# slave.net
KiCad netlist of a schematic drawn in Altium Designer
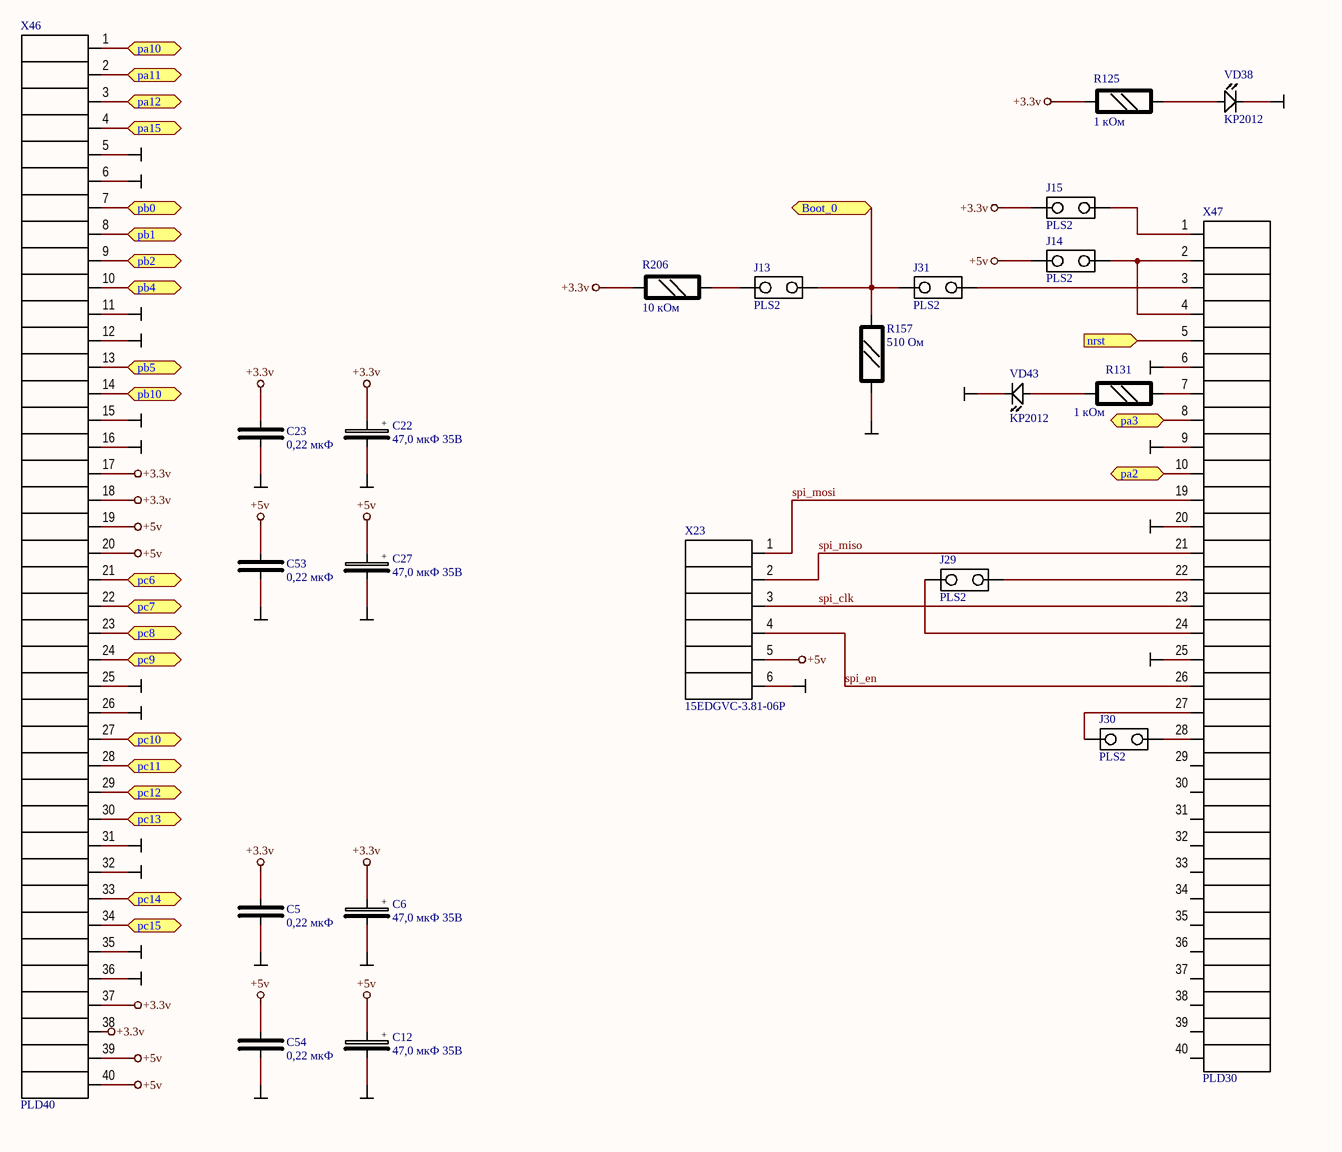
[diagram p0: slave.SchDoc]

(export (version "E")
  (design (tool "Eeschema 10.0.6"))
  (components
    (comp (ref "C5")
      (value "0,22 мкФ")
      (footprint "SMD0805CAP")
      (description "Чип конденсатор 0805")
      (fields (field (name "VOLTAGE") "50V"))
      (libsource (lib "SL02_22F") (part "C0805"))
    )
    (comp (ref "C6")
      (value "47,0 мкФ 35В")
      (footprint "cap6")
      (description "5мм Электролитический конденсатор")
      (libsource (lib "SL02_22F") (part "C_e"))
    )
    (comp (ref "C12")
      (value "47,0 мкФ 35В")
      (footprint "cap6")
      (description "5мм Электролитический конденсатор")
      (libsource (lib "SL02_22F") (part "C_e"))
    )
    (comp (ref "C22")
      (value "47,0 мкФ 35В")
      (footprint "cap6")
      (description "5мм Электролитический конденсатор")
      (libsource (lib "SL02_22F") (part "C_e"))
    )
    (comp (ref "C23")
      (value "0,22 мкФ")
      (footprint "SMD0805CAP")
      (description "Чип конденсатор 0805")
      (fields (field (name "VOLTAGE") "50V"))
      (libsource (lib "SL02_22F") (part "C0805"))
    )
    (comp (ref "C27")
      (value "47,0 мкФ 35В")
      (footprint "cap6")
      (description "5мм Электролитический конденсатор")
      (libsource (lib "SL02_22F") (part "C_e"))
    )
    (comp (ref "C53")
      (value "0,22 мкФ")
      (footprint "SMD0805CAP")
      (description "Чип конденсатор 0805")
      (fields (field (name "VOLTAGE") "50V"))
      (libsource (lib "SL02_22F") (part "C0805"))
    )
    (comp (ref "C54")
      (value "0,22 мкФ")
      (footprint "SMD0805CAP")
      (description "Чип конденсатор 0805")
      (fields (field (name "VOLTAGE") "50V"))
      (libsource (lib "SL02_22F") (part "C0805"))
    )
    (comp (ref "J13")
      (value "PLS2")
      (footprint "PLS2")
      (description "Джампер PLS2 2.54мм")
      (libsource (lib "L02_22F") (part "PLS2"))
    )
    (comp (ref "J14")
      (value "PLS2")
      (footprint "PLS2")
      (description "Джампер PLS2 2.54мм")
      (libsource (lib "L02_22F") (part "PLS2"))
    )
    (comp (ref "J15")
      (value "PLS2")
      (footprint "PLS2")
      (description "Джампер PLS2 2.54мм")
      (libsource (lib "L02_22F") (part "PLS2"))
    )
    (comp (ref "J29")
      (value "PLS2")
      (footprint "PLS2")
      (description "Джампер PLS2 2.54мм")
      (libsource (lib "L02_22F") (part "PLS2"))
    )
    (comp (ref "J30")
      (value "PLS2")
      (footprint "PLS2")
      (description "Джампер PLS2 2.54мм")
      (libsource (lib "L02_22F") (part "PLS2"))
    )
    (comp (ref "J31")
      (value "PLS2")
      (footprint "PLS2")
      (description "Джампер PLS2 2.54мм")
      (libsource (lib "L02_22F") (part "PLS2"))
    )
    (comp (ref "R125")
      (value "1 кОм")
      (footprint "SMD0805RES")
      (description "Чип резистор 0805")
      (fields (field (name "TOLERANCE") "5%"))
      (libsource (lib "SL02_22F") (part "R0805"))
    )
    (comp (ref "R131")
      (value "1 кОм")
      (footprint "SMD0805RES")
      (description "Чип резистор 0805")
      (fields (field (name "TOLERANCE") "5%"))
      (libsource (lib "SL02_22F") (part "R0805"))
    )
    (comp (ref "R157")
      (value "510 Ом")
      (footprint "SMD0805RES")
      (description "Чип резистор 0805")
      (fields (field (name "TOLERANCE") "5%"))
      (libsource (lib "SL02_22F") (part "R0805"))
    )
    (comp (ref "R206")
      (value "10 кОм")
      (footprint "SMD0805RES")
      (description "Чип резистор 0805")
      (fields (field (name "TOLERANCE") "5%"))
      (libsource (lib "SL02_22F") (part "R0805"))
    )
    (comp (ref "VD38")
      (value "KP2012")
      (footprint "SMD0805DIO_C")
      (description "Чип светодиод 0805")
      (libsource (lib "L02_22F") (part "KP2012_C"))
    )
    (comp (ref "VD43")
      (value "KP2012")
      (footprint "SMD0805DIO_C")
      (description "Чип светодиод 0805")
      (libsource (lib "L02_22F") (part "KP2012_C"))
    )
    (comp (ref "X23")
      (value "15EDGVC-3.81-06P")
      (footprint "15EDGVC_081_6")
      (description "Вилка  6/3.81")
      (fields (field (name "VOLTAGE") "2кВ"))
      (libsource (lib "L02_22F") (part "15EDGVC-3.81-06P"))
    )
    (comp (ref "X46")
      (value "PLD40")
      (footprint "PLD40_n")
      (description "Вилка  PLD 40/2.54")
      (libsource (lib "L02_22F") (part "PLD40"))
    )
    (comp (ref "X47")
      (value "PLD30")
      (footprint "PLD40")
      (description "Вилка  PLD 30/2.54")
      (libsource (lib "L02_22F") (part "PLD30"))
    )
  )
  (nets
    (net (code "1") (name "+3.3v") (class "Default")
      (node (ref "C22") (pin "1") (pinfunction "+_1") (pintype "passive"))
      (node (ref "C23") (pin "1") (pinfunction "1_1") (pintype "passive"))
      (node (ref "C5") (pin "1") (pinfunction "1_1") (pintype "passive"))
      (node (ref "C6") (pin "1") (pinfunction "+_1") (pintype "passive"))
      (node (ref "J15") (pin "1") (pinfunction "1_1") (pintype "passive"))
      (node (ref "R125") (pin "2") (pinfunction "2_2") (pintype "passive"))
      (node (ref "R206") (pin "2") (pinfunction "2_2") (pintype "passive"))
      (node (ref "X46") (pin "17") (pinfunction "17_17") (pintype "passive"))
      (node (ref "X46") (pin "18") (pinfunction "18_18") (pintype "passive"))
      (node (ref "X46") (pin "37") (pinfunction "37_37") (pintype "passive"))
      (node (ref "X46") (pin "38") (pinfunction "38_38") (pintype "passive"))
    )
    (net (code "2") (name "+5v") (class "Default")
      (node (ref "C12") (pin "1") (pinfunction "+_1") (pintype "passive"))
      (node (ref "C27") (pin "1") (pinfunction "+_1") (pintype "passive"))
      (node (ref "C53") (pin "1") (pinfunction "1_1") (pintype "passive"))
      (node (ref "C54") (pin "1") (pinfunction "1_1") (pintype "passive"))
      (node (ref "J14") (pin "1") (pinfunction "1_1") (pintype "passive"))
      (node (ref "X23") (pin "5") (pinfunction "5_5") (pintype "passive"))
      (node (ref "X46") (pin "19") (pinfunction "19_19") (pintype "passive"))
      (node (ref "X46") (pin "20") (pinfunction "20_20") (pintype "passive"))
      (node (ref "X46") (pin "39") (pinfunction "39_39") (pintype "passive"))
      (node (ref "X46") (pin "40") (pinfunction "40_40") (pintype "passive"))
    )
    (net (code "3") (name "/nrst") (class "Default")
      (node (ref "X47") (pin "5") (pinfunction "5_5") (pintype "passive"))
    )
    (net (code "4") (name "/pa2") (class "Default")
      (node (ref "X47") (pin "10") (pinfunction "10_10") (pintype "passive"))
    )
    (net (code "5") (name "/pa3") (class "Default")
      (node (ref "X47") (pin "8") (pinfunction "8_8") (pintype "passive"))
    )
    (net (code "6") (name "/pa10") (class "Default")
      (node (ref "X46") (pin "1") (pinfunction "1_1") (pintype "passive"))
    )
    (net (code "7") (name "/pa11") (class "Default")
      (node (ref "X46") (pin "2") (pinfunction "2_2") (pintype "passive"))
    )
    (net (code "8") (name "/pa12") (class "Default")
      (node (ref "X46") (pin "3") (pinfunction "3_3") (pintype "passive"))
    )
    (net (code "9") (name "/pa15") (class "Default")
      (node (ref "X46") (pin "4") (pinfunction "4_4") (pintype "passive"))
    )
    (net (code "10") (name "/pb0") (class "Default")
      (node (ref "X46") (pin "7") (pinfunction "7_7") (pintype "passive"))
    )
    (net (code "11") (name "/pb1") (class "Default")
      (node (ref "X46") (pin "8") (pinfunction "8_8") (pintype "passive"))
    )
    (net (code "12") (name "/pb2") (class "Default")
      (node (ref "X46") (pin "9") (pinfunction "9_9") (pintype "passive"))
    )
    (net (code "13") (name "/pb4") (class "Default")
      (node (ref "X46") (pin "10") (pinfunction "10_10") (pintype "passive"))
    )
    (net (code "14") (name "/pb5") (class "Default")
      (node (ref "X46") (pin "13") (pinfunction "13_13") (pintype "passive"))
    )
    (net (code "15") (name "/pb10") (class "Default")
      (node (ref "X46") (pin "14") (pinfunction "14_14") (pintype "passive"))
    )
    (net (code "16") (name "/pс6") (class "Default")
      (node (ref "X46") (pin "21") (pinfunction "21_21") (pintype "passive"))
    )
    (net (code "17") (name "/pс7") (class "Default")
      (node (ref "X46") (pin "22") (pinfunction "22_22") (pintype "passive"))
    )
    (net (code "18") (name "/pс8") (class "Default")
      (node (ref "X46") (pin "23") (pinfunction "23_23") (pintype "passive"))
    )
    (net (code "19") (name "/pс9") (class "Default")
      (node (ref "X46") (pin "24") (pinfunction "24_24") (pintype "passive"))
    )
    (net (code "20") (name "/pс10") (class "Default")
      (node (ref "X46") (pin "27") (pinfunction "27_27") (pintype "passive"))
    )
    (net (code "21") (name "/pс11") (class "Default")
      (node (ref "X46") (pin "28") (pinfunction "28_28") (pintype "passive"))
    )
    (net (code "22") (name "/pс12") (class "Default")
      (node (ref "X46") (pin "29") (pinfunction "29_29") (pintype "passive"))
    )
    (net (code "23") (name "/pс13") (class "Default")
      (node (ref "X46") (pin "30") (pinfunction "30_30") (pintype "passive"))
    )
    (net (code "24") (name "/pс14") (class "Default")
      (node (ref "X46") (pin "33") (pinfunction "33_33") (pintype "passive"))
    )
    (net (code "25") (name "/pс15") (class "Default")
      (node (ref "X46") (pin "34") (pinfunction "34_34") (pintype "passive"))
    )
    (net (code "26") (name "/spi_clk") (class "Default")
      (node (ref "X23") (pin "3") (pinfunction "3_3") (pintype "passive"))
      (node (ref "X47") (pin "23") (pinfunction "23_23") (pintype "passive"))
    )
    (net (code "27") (name "/spi_en") (class "Default")
      (node (ref "X23") (pin "4") (pinfunction "4_4") (pintype "passive"))
      (node (ref "X47") (pin "26") (pinfunction "26_26") (pintype "passive"))
    )
    (net (code "28") (name "/spi_miso") (class "Default")
      (node (ref "X23") (pin "2") (pinfunction "2_2") (pintype "passive"))
      (node (ref "X47") (pin "21") (pinfunction "21_21") (pintype "passive"))
    )
    (net (code "29") (name "/spi_mosi") (class "Default")
      (node (ref "X23") (pin "1") (pinfunction "1_1") (pintype "passive"))
      (node (ref "X47") (pin "19") (pinfunction "19_19") (pintype "passive"))
    )
    (net (code "30") (name "/Вооt_0") (class "Default")
      (node (ref "J13") (pin "1") (pinfunction "1_1") (pintype "passive"))
      (node (ref "J31") (pin "2") (pinfunction "2_2") (pintype "passive"))
      (node (ref "R157") (pin "1") (pinfunction "1_1") (pintype "passive"))
    )
    (net (code "31") (name "GND") (class "Default")
      (node (ref "C12") (pin "2") (pinfunction "-_2") (pintype "passive"))
      (node (ref "C22") (pin "2") (pinfunction "-_2") (pintype "passive"))
      (node (ref "C23") (pin "2") (pinfunction "2_2") (pintype "passive"))
      (node (ref "C27") (pin "2") (pinfunction "-_2") (pintype "passive"))
      (node (ref "C5") (pin "2") (pinfunction "2_2") (pintype "passive"))
      (node (ref "C53") (pin "2") (pinfunction "2_2") (pintype "passive"))
      (node (ref "C54") (pin "2") (pinfunction "2_2") (pintype "passive"))
      (node (ref "C6") (pin "2") (pinfunction "-_2") (pintype "passive"))
      (node (ref "R157") (pin "2") (pinfunction "2_2") (pintype "passive"))
      (node (ref "VD38") (pin "1") (pinfunction "Cathode_1") (pintype "passive"))
      (node (ref "VD43") (pin "1") (pinfunction "Cathode_1") (pintype "passive"))
      (node (ref "X23") (pin "6") (pinfunction "6_6") (pintype "passive"))
      (node (ref "X46") (pin "11") (pinfunction "11_11") (pintype "passive"))
      (node (ref "X46") (pin "12") (pinfunction "12_12") (pintype "passive"))
      (node (ref "X46") (pin "15") (pinfunction "15_15") (pintype "passive"))
      (node (ref "X46") (pin "16") (pinfunction "16_16") (pintype "passive"))
      (node (ref "X46") (pin "25") (pinfunction "25_25") (pintype "passive"))
      (node (ref "X46") (pin "26") (pinfunction "26_26") (pintype "passive"))
      (node (ref "X46") (pin "31") (pinfunction "31_31") (pintype "passive"))
      (node (ref "X46") (pin "32") (pinfunction "32_32") (pintype "passive"))
      (node (ref "X46") (pin "35") (pinfunction "35_35") (pintype "passive"))
      (node (ref "X46") (pin "36") (pinfunction "36_36") (pintype "passive"))
      (node (ref "X46") (pin "5") (pinfunction "5_5") (pintype "passive"))
      (node (ref "X46") (pin "6") (pinfunction "6_6") (pintype "passive"))
      (node (ref "X47") (pin "20") (pinfunction "20_20") (pintype "passive"))
      (node (ref "X47") (pin "25") (pinfunction "25_25") (pintype "passive"))
      (node (ref "X47") (pin "6") (pinfunction "6_6") (pintype "passive"))
      (node (ref "X47") (pin "9") (pinfunction "9_9") (pintype "passive"))
    )
    (net (code "32") (name "Net-(J13-Pad2)") (class "Default")
      (node (ref "J13") (pin "2") (pinfunction "2_2") (pintype "passive"))
      (node (ref "R206") (pin "1") (pinfunction "1_1") (pintype "passive"))
    )
    (net (code "33") (name "Net-(J14-Pad2)") (class "Default")
      (node (ref "J14") (pin "2") (pinfunction "2_2") (pintype "passive"))
      (node (ref "X47") (pin "2") (pinfunction "2_2") (pintype "passive"))
      (node (ref "X47") (pin "4") (pinfunction "4_4") (pintype "passive"))
    )
    (net (code "34") (name "Net-(J15-Pad2)") (class "Default")
      (node (ref "J15") (pin "2") (pinfunction "2_2") (pintype "passive"))
      (node (ref "X47") (pin "1") (pinfunction "1_1") (pintype "passive"))
    )
    (net (code "35") (name "Net-(J29-Pad1)") (class "Default")
      (node (ref "J29") (pin "1") (pinfunction "1_1") (pintype "passive"))
      (node (ref "X47") (pin "24") (pinfunction "24_24") (pintype "passive"))
    )
    (net (code "36") (name "Net-(J29-Pad2)") (class "Default")
      (node (ref "J29") (pin "2") (pinfunction "2_2") (pintype "passive"))
      (node (ref "X47") (pin "22") (pinfunction "22_22") (pintype "passive"))
    )
    (net (code "37") (name "Net-(J30-Pad1)") (class "Default")
      (node (ref "J30") (pin "1") (pinfunction "1_1") (pintype "passive"))
      (node (ref "X47") (pin "27") (pinfunction "27_27") (pintype "passive"))
    )
    (net (code "38") (name "Net-(J30-Pad2)") (class "Default")
      (node (ref "J30") (pin "2") (pinfunction "2_2") (pintype "passive"))
      (node (ref "X47") (pin "28") (pinfunction "28_28") (pintype "passive"))
    )
    (net (code "39") (name "Net-(J31-Pad1)") (class "Default")
      (node (ref "J31") (pin "1") (pinfunction "1_1") (pintype "passive"))
      (node (ref "X47") (pin "3") (pinfunction "3_3") (pintype "passive"))
    )
    (net (code "40") (name "Net-(R131-Pad1)") (class "Default")
      (node (ref "R131") (pin "1") (pinfunction "1_1") (pintype "passive"))
      (node (ref "X47") (pin "7") (pinfunction "7_7") (pintype "passive"))
    )
    (net (code "41") (name "Net-(VD38-Anode)") (class "Default")
      (node (ref "R125") (pin "1") (pinfunction "1_1") (pintype "passive"))
      (node (ref "VD38") (pin "2") (pinfunction "Anode_2") (pintype "passive"))
    )
    (net (code "42") (name "Net-(VD43-Anode)") (class "Default")
      (node (ref "R131") (pin "2") (pinfunction "2_2") (pintype "passive"))
      (node (ref "VD43") (pin "2") (pinfunction "Anode_2") (pintype "passive"))
    )
    (net (code "43") (name "unconnected-(X47-Pad29)") (class "Default")
      (node (ref "X47") (pin "29") (pinfunction "29_29") (pintype "passive"))
    )
    (net (code "44") (name "unconnected-(X47-Pad30)") (class "Default")
      (node (ref "X47") (pin "30") (pinfunction "30_30") (pintype "passive"))
    )
    (net (code "45") (name "unconnected-(X47-Pad31)") (class "Default")
      (node (ref "X47") (pin "31") (pinfunction "31_31") (pintype "passive"))
    )
    (net (code "46") (name "unconnected-(X47-Pad32)") (class "Default")
      (node (ref "X47") (pin "32") (pinfunction "32_32") (pintype "passive"))
    )
    (net (code "47") (name "unconnected-(X47-Pad33)") (class "Default")
      (node (ref "X47") (pin "33") (pinfunction "33_33") (pintype "passive"))
    )
    (net (code "48") (name "unconnected-(X47-Pad34)") (class "Default")
      (node (ref "X47") (pin "34") (pinfunction "34_34") (pintype "passive"))
    )
    (net (code "49") (name "unconnected-(X47-Pad35)") (class "Default")
      (node (ref "X47") (pin "35") (pinfunction "35_35") (pintype "passive"))
    )
    (net (code "50") (name "unconnected-(X47-Pad36)") (class "Default")
      (node (ref "X47") (pin "36") (pinfunction "36_36") (pintype "passive"))
    )
    (net (code "51") (name "unconnected-(X47-Pad37)") (class "Default")
      (node (ref "X47") (pin "37") (pinfunction "37_37") (pintype "passive"))
    )
    (net (code "52") (name "unconnected-(X47-Pad38)") (class "Default")
      (node (ref "X47") (pin "38") (pinfunction "38_38") (pintype "passive"))
    )
    (net (code "53") (name "unconnected-(X47-Pad39)") (class "Default")
      (node (ref "X47") (pin "39") (pinfunction "39_39") (pintype "passive"))
    )
    (net (code "54") (name "unconnected-(X47-Pad40)") (class "Default")
      (node (ref "X47") (pin "40") (pinfunction "40_40") (pintype "passive"))
    )
  )
)
